# UART_LORA.net
KiCad netlist of a schematic drawn in Altium Designer
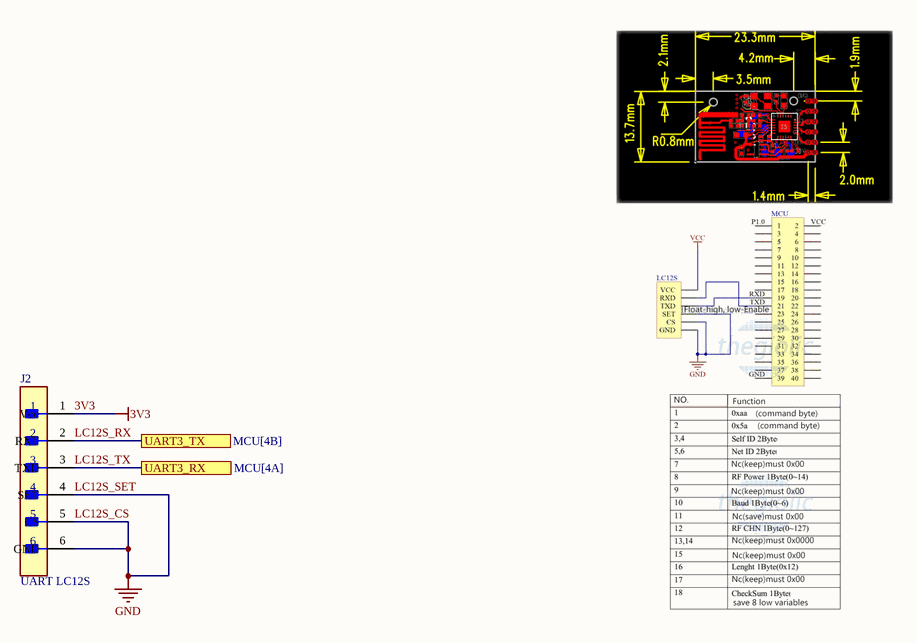
[diagram p0: UART LORA.SchDoc]

(export (version "E")
  (design (tool "Eeschema 10.0.6"))
  (components
    (comp (ref "J2")
      (value "UART LC12S")
      (footprint "FP-22-28-4060-MFG")
      (description "KK 254 Breakaway Header, Vertical, 6 Circuits, Tin (Sn) Plating, Mating Pin Length 6.09mm")
      (libsource (lib "Ho Chi Minh University of Technology") (part "f2cb566baf1c37ab5a3b8e90bbeafd6"))
    )
  )
  (nets
    (net (code "1") (name "/LC12S_RX") (class "Default")
      (node (ref "J2") (pin "2") (pinfunction "RXT_2") (pintype "passive"))
    )
    (net (code "2") (name "/LC12S_TX") (class "Default")
      (node (ref "J2") (pin "3") (pinfunction "TXD_3") (pintype "passive"))
    )
    (net (code "3") (name "3V3") (class "Default")
      (node (ref "J2") (pin "1") (pinfunction "Vcc_1") (pintype "passive"))
    )
    (net (code "4") (name "GND") (class "Default")
      (node (ref "J2") (pin "4") (pinfunction "SET_4") (pintype "passive"))
      (node (ref "J2") (pin "5") (pinfunction "CS_5") (pintype "passive"))
      (node (ref "J2") (pin "6") (pinfunction "GND_6") (pintype "passive"))
    )
  )
)
